# DM1090FFC_USB.net
KiCad netlist of a schematic drawn in Altium Designer
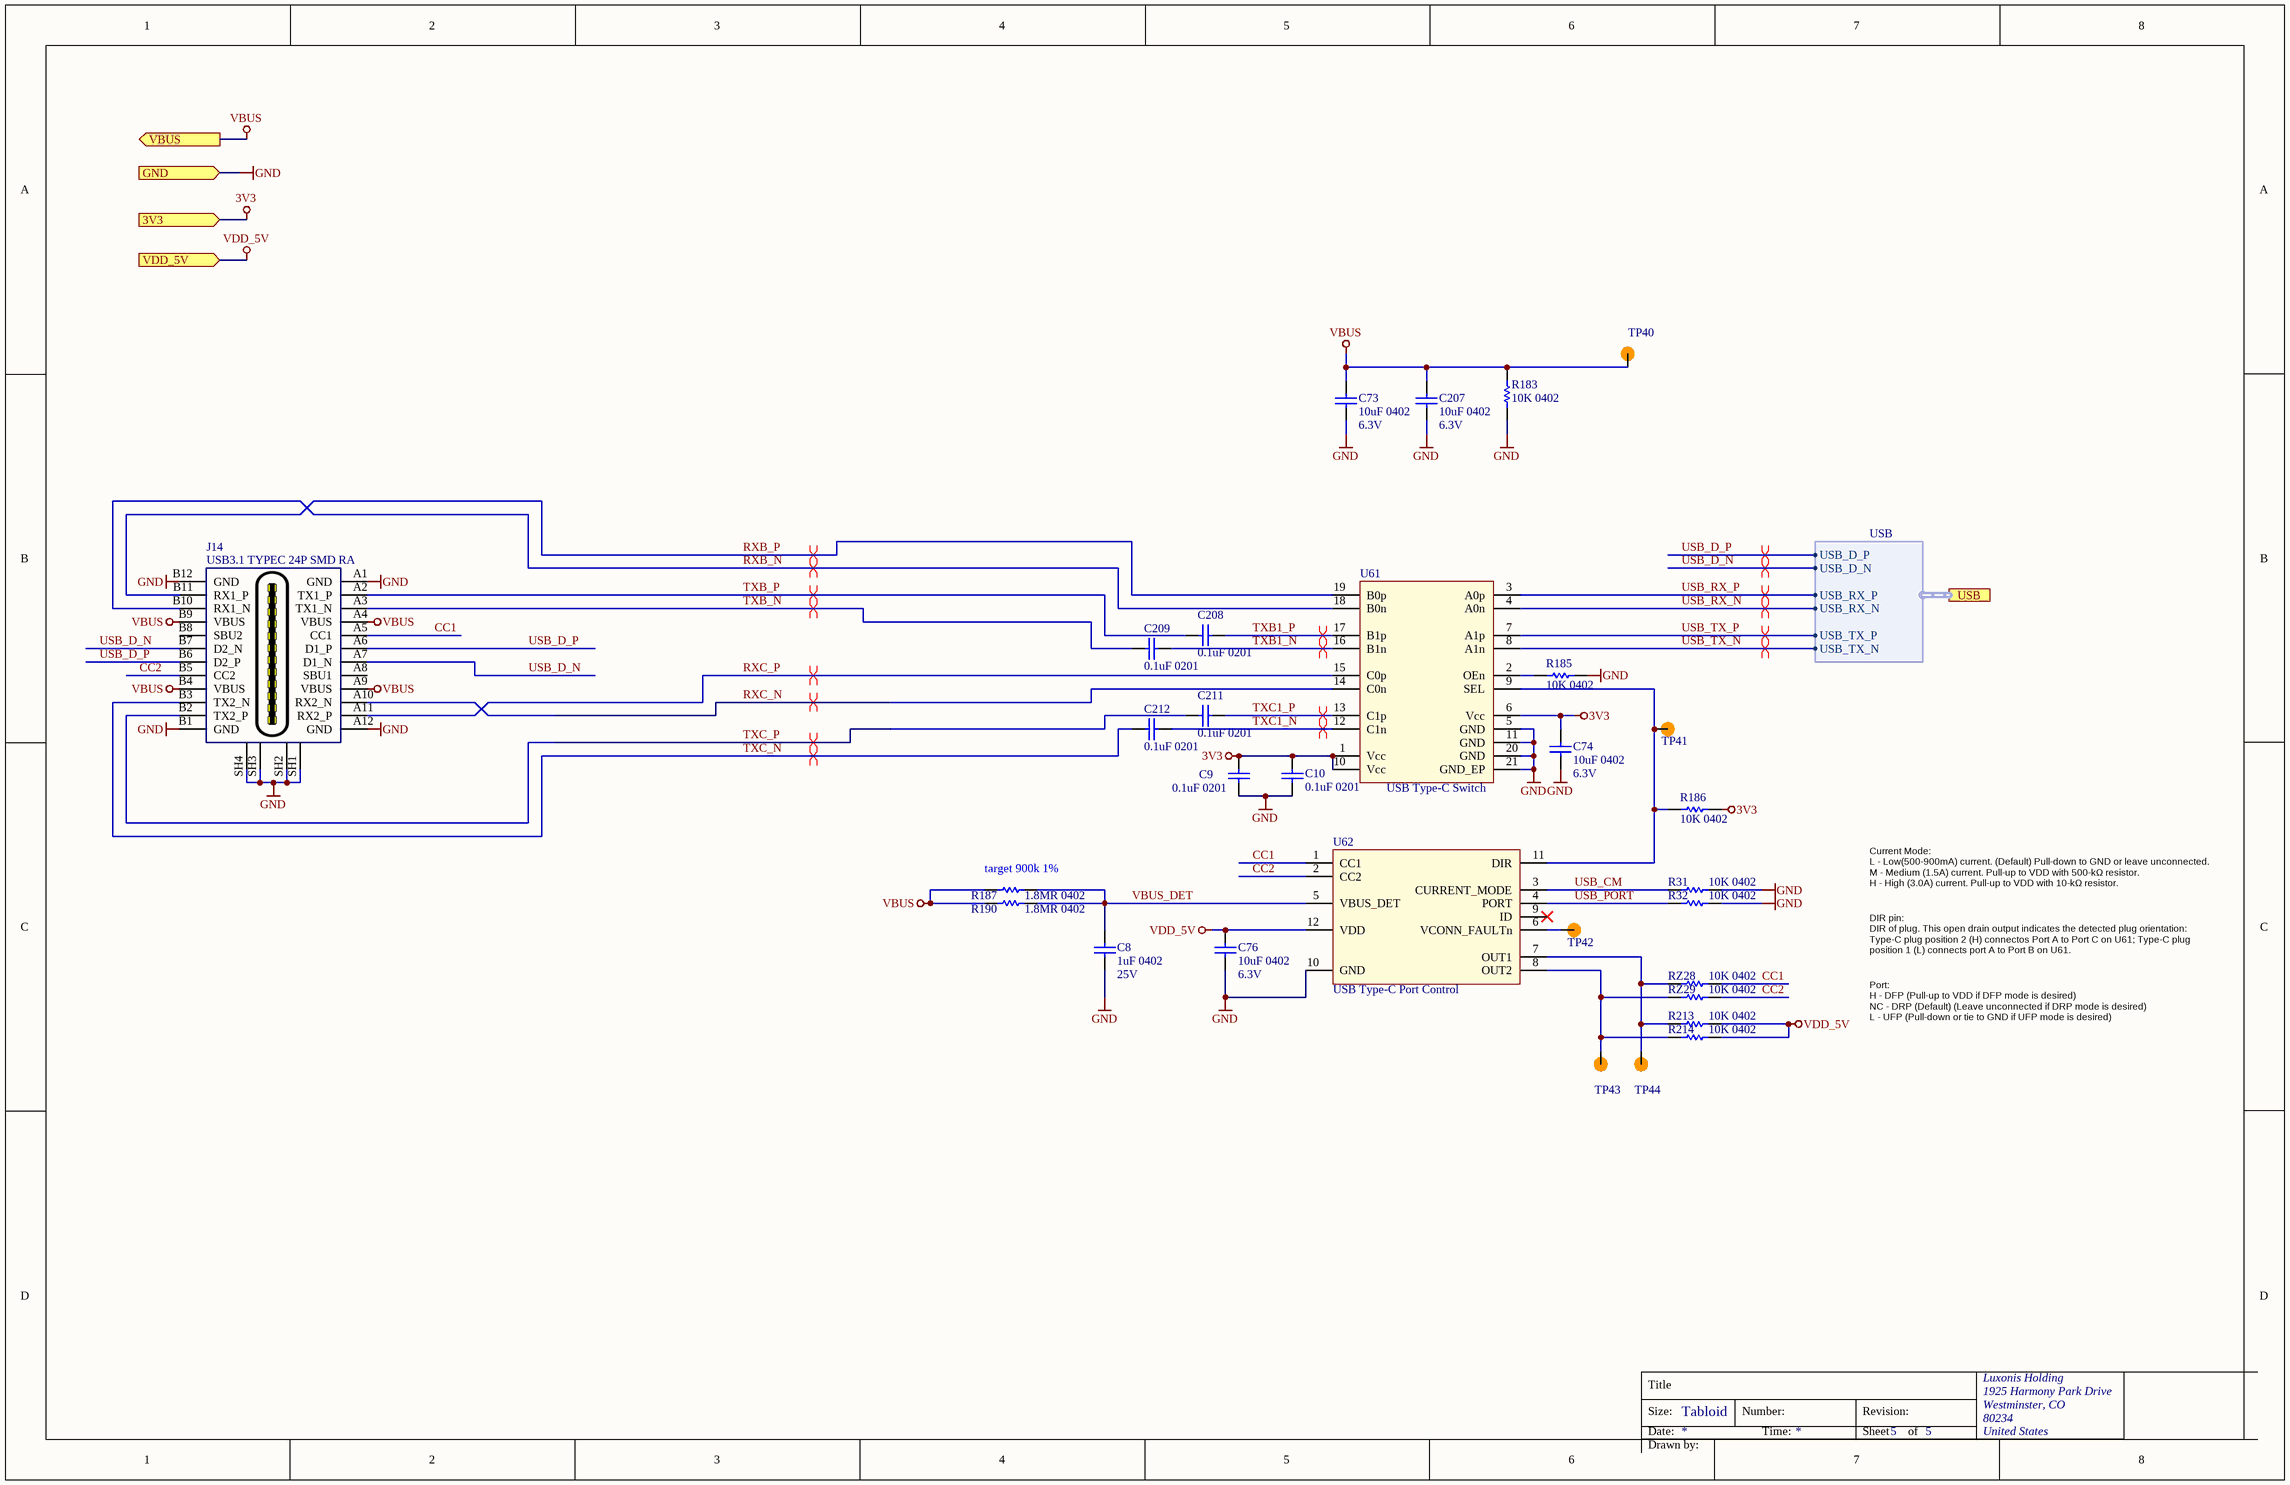
[diagram p0: DM1090FFC_USB.SchDoc]

(export (version "E")
  (design (tool "Eeschema 10.0.6"))
  (components
    (comp (ref "C8")
      (value "1uF 0402")
      (footprint "CAP_Altium_Vault_Generic:CAPC0402(1005)70_N")
      (description "CAP CER 1UF 25V X5R 0402 10%")
      (fields
        (field (name "TOLERANCE") "10%")
        (field (name "VOLTAGE") "25V")
        (field (name "VOLTAGE RATING") "25V")
      )
      (libsource (lib "LuxonisMaster") (part "GRM155R61E105KA12D"))
    )
    (comp (ref "C9")
      (value "0.1uF 0201")
      (footprint "CAP_Altium_Vault_Generic:CAPC0201(0603)33_L")
      (description "CAP CER 0.1UF 10V X5R 0201")
      (fields (field (name "TOLERANCE") "10%") (field (name "VOLTAGE") "10V"))
      (libsource (lib "LuxonisMaster") (part "GRM033R61A104KE15D"))
    )
    (comp (ref "C10")
      (value "0.1uF 0201")
      (footprint "CAP_Altium_Vault_Generic:CAPC0201(0603)33_L")
      (description "CAP CER 0.1UF 10V X5R 0201")
      (fields (field (name "TOLERANCE") "10%") (field (name "VOLTAGE") "10V"))
      (libsource (lib "LuxonisMaster") (part "GRM033R61A104KE15D"))
    )
    (comp (ref "C73")
      (value "10uF 0402")
      (footprint "CAP_Altium_Vault_Generic:CAPC0402(1005)70_N")
      (description "CAP CER 10UF 6.3V X5R 0402 20%")
      (fields (field (name "TOLERANCE") "20%") (field (name "VOLTAGE RATING") "6.3V"))
      (libsource (lib "LuxonisMaster") (part "GRM155R60J106ME15D"))
    )
    (comp (ref "C74")
      (value "10uF 0402")
      (footprint "CAP_Altium_Vault_Generic:CAPC0402(1005)70_N")
      (description "CAP CER 10UF 6.3V X5R 0402 20%")
      (fields (field (name "TOLERANCE") "20%") (field (name "VOLTAGE RATING") "6.3V"))
      (libsource (lib "LuxonisMaster") (part "GRM155R60J106ME15D"))
    )
    (comp (ref "C76")
      (value "10uF 0402")
      (footprint "CAP_Altium_Vault_Generic:CAPC0402(1005)70_N")
      (description "CAP CER 10UF 6.3V X5R 0402 20%")
      (fields (field (name "TOLERANCE") "20%") (field (name "VOLTAGE RATING") "6.3V"))
      (libsource (lib "LuxonisMaster") (part "GRM155R60J106ME15D"))
    )
    (comp (ref "C207")
      (value "10uF 0402")
      (footprint "CAP_Altium_Vault_Generic:CAPC0402(1005)70_N")
      (description "CAP CER 10UF 6.3V X5R 0402 20%")
      (fields (field (name "TOLERANCE") "20%") (field (name "VOLTAGE RATING") "6.3V"))
      (libsource (lib "LuxonisMaster") (part "GRM155R60J106ME15D"))
    )
    (comp (ref "C208")
      (value "0.1uF 0201")
      (footprint "CAP_Altium_Vault_Generic:CAPC0201(0603)33_L")
      (description "CAP CER 0.1UF 10V X5R 0201")
      (fields (field (name "TOLERANCE") "10%") (field (name "VOLTAGE") "10V"))
      (libsource (lib "LuxonisMaster") (part "GRM033R61A104KE15D"))
    )
    (comp (ref "C209")
      (value "0.1uF 0201")
      (footprint "CAP_Altium_Vault_Generic:CAPC0201(0603)33_L")
      (description "CAP CER 0.1UF 10V X5R 0201")
      (fields (field (name "TOLERANCE") "10%") (field (name "VOLTAGE") "10V"))
      (libsource (lib "LuxonisMaster") (part "GRM033R61A104KE15D"))
    )
    (comp (ref "C211")
      (value "0.1uF 0201")
      (footprint "CAP_Altium_Vault_Generic:CAPC0201(0603)33_L")
      (description "CAP CER 0.1UF 10V X5R 0201")
      (fields (field (name "TOLERANCE") "10%") (field (name "VOLTAGE") "10V"))
      (libsource (lib "LuxonisMaster") (part "GRM033R61A104KE15D"))
    )
    (comp (ref "C212")
      (value "0.1uF 0201")
      (footprint "CAP_Altium_Vault_Generic:CAPC0201(0603)33_L")
      (description "CAP CER 0.1UF 10V X5R 0201")
      (fields (field (name "TOLERANCE") "10%") (field (name "VOLTAGE") "10V"))
      (libsource (lib "LuxonisMaster") (part "GRM033R61A104KE15D"))
    )
    (comp (ref "J14")
      (value "USB3.1 TYPEC 24P SMD RA")
      (footprint "LuxonisMaster:105450-0101")
      (description "CONN RCP USB3.1 TYPEC 24P SMD RA")
      (libsource (lib "LuxonisMaster") (part "105450-0101"))
    )
    (comp (ref "R31")
      (value "10K 0402")
      (footprint "RES_Altium_Vault_Generic:RESC0402(1005)_N")
      (fields (field (name "TOLERANCE") "1%"))
      (libsource (lib "LuxonisMaster") (part "RC0402FR-1310KL"))
    )
    (comp (ref "R32")
      (value "10K 0402")
      (footprint "RES_Altium_Vault_Generic:RESC0402(1005)_N")
      (fields (field (name "TOLERANCE") "1%"))
      (libsource (lib "LuxonisMaster") (part "RC0402FR-1310KL"))
    )
    (comp (ref "R183")
      (value "10K 0402")
      (footprint "RES_Altium_Vault_Generic:RESC0402(1005)_N")
      (fields (field (name "TOLERANCE") "1%"))
      (libsource (lib "LuxonisMaster") (part "RC0402FR-1310KL"))
    )
    (comp (ref "R185")
      (value "10K 0402")
      (footprint "RES_Altium_Vault_Generic:RESC0402(1005)_N")
      (fields (field (name "TOLERANCE") "1%"))
      (libsource (lib "LuxonisMaster") (part "RC0402FR-1310KL"))
    )
    (comp (ref "R186")
      (value "10K 0402")
      (footprint "RES_Altium_Vault_Generic:RESC0402(1005)_N")
      (fields (field (name "TOLERANCE") "1%"))
      (libsource (lib "LuxonisMaster") (part "RC0402FR-1310KL"))
    )
    (comp (ref "R187")
      (value "1.8MR 0402")
      (footprint "RES_Altium_Vault_Generic:RESC0402(1005)_N")
      (description "RES SMD 1.8M OHM 1% 1/16W 0402")
      (fields (field (name "TOLERANCE") "1%"))
      (libsource (lib "LuxonisMaster") (part "CRCW04021M80FKED"))
    )
    (comp (ref "R190")
      (value "1.8MR 0402")
      (footprint "RES_Altium_Vault_Generic:RESC0402(1005)_N")
      (description "RES SMD 1.8M OHM 1% 1/16W 0402")
      (fields (field (name "TOLERANCE") "1%"))
      (libsource (lib "LuxonisMaster") (part "CRCW04021M80FKED"))
    )
    (comp (ref "R213")
      (value "10K 0402")
      (footprint "RES_Altium_Vault_Generic:RESC0402(1005)_N")
      (fields (field (name "TOLERANCE") "1%"))
      (libsource (lib "LuxonisMaster") (part "RC0402FR-1310KL"))
    )
    (comp (ref "R214")
      (value "10K 0402")
      (footprint "RES_Altium_Vault_Generic:RESC0402(1005)_N")
      (fields (field (name "TOLERANCE") "1%"))
      (libsource (lib "LuxonisMaster") (part "RC0402FR-1310KL"))
    )
    (comp (ref "RZ28")
      (value "10K 0402")
      (footprint "RES_Altium_Vault_Generic:RESC0402(1005)_N")
      (fields (field (name "TOLERANCE") "1%"))
      (libsource (lib "LuxonisMaster") (part "RC0402FR-1310KL"))
    )
    (comp (ref "RZ29")
      (value "10K 0402")
      (footprint "RES_Altium_Vault_Generic:RESC0402(1005)_N")
      (fields (field (name "TOLERANCE") "1%"))
      (libsource (lib "LuxonisMaster") (part "RC0402FR-1310KL"))
    )
    (comp (ref "TP40")
      (value "TP100_200_NS")
      (footprint "LuxonisMaster:TP100_200_NS")
      (libsource (lib "LuxonisMaster") (part "TEST_POINT"))
    )
    (comp (ref "TP41")
      (value "TP100_200_NS")
      (footprint "LuxonisMaster:TP100_200_NS")
      (libsource (lib "LuxonisMaster") (part "TEST_POINT"))
    )
    (comp (ref "TP42")
      (value "TP100_200_NS")
      (footprint "LuxonisMaster:TP100_200_NS")
      (libsource (lib "LuxonisMaster") (part "TEST_POINT"))
    )
    (comp (ref "TP43")
      (value "TP100_200_NS")
      (footprint "LuxonisMaster:TP100_200_NS")
      (libsource (lib "LuxonisMaster") (part "TEST_POINT"))
    )
    (comp (ref "TP44")
      (value "TP100_200_NS")
      (footprint "LuxonisMaster:TP100_200_NS")
      (libsource (lib "LuxonisMaster") (part "TEST_POINT"))
    )
    (comp (ref "U61")
      (value "USB Type-C Switch")
      (footprint "CBTL02043A")
      (libsource (lib "LuxonisMaster") (part "CBTL02043A"))
    )
    (comp (ref "U62")
      (value "USB Type-C Port Control")
      (footprint "LuxonisMaster:TUSB321RWBR")
      (description "IC USB PORT CONTROL TYPE-C 12X2Q")
      (libsource (lib "LuxonisMaster") (part "TUSB321RWBR"))
    )
  )
  (nets
    (net (code "2") (name "/CC1") (class "Default")
      (node (ref "J14") (pin "A5") (pinfunction "CC1_A5") (pintype "passive"))
      (node (ref "RZ28") (pin "2") (pinfunction "2_2") (pintype "passive"))
      (node (ref "U62") (pin "1") (pinfunction "CC1_1") (pintype "passive"))
    )
    (net (code "3") (name "/CC2") (class "Default")
      (node (ref "J14") (pin "B5") (pinfunction "CC2_B5") (pintype "passive"))
      (node (ref "RZ29") (pin "2") (pinfunction "2_2") (pintype "passive"))
      (node (ref "U62") (pin "2") (pinfunction "CC2_2") (pintype "passive"))
    )
    (net (code "4") (name "/RXB_N") (class "Default")
      (node (ref "J14") (pin "B10") (pinfunction "RX1_N_B10") (pintype "passive"))
      (node (ref "U61") (pin "18") (pinfunction "B0n_18") (pintype "passive"))
    )
    (net (code "5") (name "/RXB_P") (class "Default")
      (node (ref "J14") (pin "B11") (pinfunction "RX1_P_B11") (pintype "passive"))
      (node (ref "U61") (pin "19") (pinfunction "B0p_19") (pintype "passive"))
    )
    (net (code "6") (name "/RXC_N") (class "Default")
      (node (ref "J14") (pin "A10") (pinfunction "RX2_N_A10") (pintype "passive"))
      (node (ref "U61") (pin "14") (pinfunction "C0n_14") (pintype "passive"))
    )
    (net (code "7") (name "/RXC_P") (class "Default")
      (node (ref "J14") (pin "A11") (pinfunction "RX2_P_A11") (pintype "passive"))
      (node (ref "U61") (pin "15") (pinfunction "C0p_15") (pintype "passive"))
    )
    (net (code "8") (name "/TXB1_N") (class "Default")
      (node (ref "C209") (pin "2") (pinfunction "2_2") (pintype "passive"))
      (node (ref "U61") (pin "16") (pinfunction "B1n_16") (pintype "passive"))
    )
    (net (code "9") (name "/TXB1_P") (class "Default")
      (node (ref "C208") (pin "2") (pinfunction "2_2") (pintype "passive"))
      (node (ref "U61") (pin "17") (pinfunction "B1p_17") (pintype "passive"))
    )
    (net (code "10") (name "/TXB_N") (class "Default")
      (node (ref "C209") (pin "1") (pinfunction "1_1") (pintype "passive"))
      (node (ref "J14") (pin "A3") (pinfunction "TX1_N_A3") (pintype "passive"))
    )
    (net (code "11") (name "/TXB_P") (class "Default")
      (node (ref "C208") (pin "1") (pinfunction "1_1") (pintype "passive"))
      (node (ref "J14") (pin "A2") (pinfunction "TX1_P_A2") (pintype "passive"))
    )
    (net (code "12") (name "/TXC1_N") (class "Default")
      (node (ref "C212") (pin "2") (pinfunction "2_2") (pintype "passive"))
      (node (ref "U61") (pin "12") (pinfunction "C1n_12") (pintype "passive"))
    )
    (net (code "13") (name "/TXC1_P") (class "Default")
      (node (ref "C211") (pin "2") (pinfunction "2_2") (pintype "passive"))
      (node (ref "U61") (pin "13") (pinfunction "C1p_13") (pintype "passive"))
    )
    (net (code "14") (name "/TXC_N") (class "Default")
      (node (ref "C212") (pin "1") (pinfunction "1_1") (pintype "passive"))
      (node (ref "J14") (pin "B3") (pinfunction "TX2_N_B3") (pintype "passive"))
    )
    (net (code "15") (name "/TXC_P") (class "Default")
      (node (ref "C211") (pin "1") (pinfunction "1_1") (pintype "passive"))
      (node (ref "J14") (pin "B2") (pinfunction "TX2_P_B2") (pintype "passive"))
    )
    (net (code "16") (name "/USB_CM") (class "Default")
      (node (ref "R31") (pin "1") (pinfunction "1_1") (pintype "passive"))
      (node (ref "U62") (pin "3") (pinfunction "CURRENT_MODE_3") (pintype "passive"))
    )
    (net (code "17") (name "/USB_D_N") (class "Default")
      (node (ref "J14") (pin "A7") (pinfunction "D1_N_A7") (pintype "passive"))
      (node (ref "J14") (pin "B7") (pinfunction "D2_N_B7") (pintype "passive"))
    )
    (net (code "18") (name "/USB_D_P") (class "Default")
      (node (ref "J14") (pin "A6") (pinfunction "D1_P_A6") (pintype "passive"))
      (node (ref "J14") (pin "B6") (pinfunction "D2_P_B6") (pintype "passive"))
    )
    (net (code "19") (name "/USB_PORT") (class "Default")
      (node (ref "R32") (pin "1") (pinfunction "1_1") (pintype "passive"))
      (node (ref "U62") (pin "4") (pinfunction "PORT_4") (pintype "passive"))
    )
    (net (code "20") (name "/USB_RX_N") (class "Default")
      (node (ref "U61") (pin "4") (pinfunction "A0n_4") (pintype "passive"))
    )
    (net (code "21") (name "/USB_RX_P") (class "Default")
      (node (ref "U61") (pin "3") (pinfunction "A0p_3") (pintype "passive"))
    )
    (net (code "22") (name "/USB_TX_N") (class "Default")
      (node (ref "U61") (pin "8") (pinfunction "A1n_8") (pintype "passive"))
    )
    (net (code "23") (name "/USB_TX_P") (class "Default")
      (node (ref "U61") (pin "7") (pinfunction "A1p_7") (pintype "passive"))
    )
    (net (code "24") (name "/VBUS_DET") (class "Default")
      (node (ref "C8") (pin "2") (pinfunction "2_2") (pintype "passive"))
      (node (ref "R187") (pin "2") (pinfunction "2_2") (pintype "passive"))
      (node (ref "R190") (pin "2") (pinfunction "2_2") (pintype "passive"))
      (node (ref "U62") (pin "5") (pinfunction "VBUS_DET_5") (pintype "passive"))
    )
    (net (code "26") (name "3V3") (class "Default")
      (node (ref "C10") (pin "2") (pinfunction "2_2") (pintype "passive"))
      (node (ref "C74") (pin "2") (pinfunction "2_2") (pintype "passive"))
      (node (ref "C9") (pin "2") (pinfunction "2_2") (pintype "passive"))
      (node (ref "R186") (pin "2") (pinfunction "2_2") (pintype "passive"))
      (node (ref "U61") (pin "1") (pinfunction "Vcc_1") (pintype "passive"))
      (node (ref "U61") (pin "10") (pinfunction "Vcc_10") (pintype "passive"))
      (node (ref "U61") (pin "6") (pinfunction "Vcc_6") (pintype "passive"))
    )
    (net (code "27") (name "GND") (class "Default")
      (node (ref "C10") (pin "1") (pinfunction "1_1") (pintype "passive"))
      (node (ref "C207") (pin "1") (pinfunction "1_1") (pintype "passive"))
      (node (ref "C73") (pin "1") (pinfunction "1_1") (pintype "passive"))
      (node (ref "C74") (pin "1") (pinfunction "1_1") (pintype "passive"))
      (node (ref "C76") (pin "1") (pinfunction "1_1") (pintype "passive"))
      (node (ref "C8") (pin "1") (pinfunction "1_1") (pintype "passive"))
      (node (ref "C9") (pin "1") (pinfunction "1_1") (pintype "passive"))
      (node (ref "J14") (pin "A1") (pinfunction "GND_A1") (pintype "passive"))
      (node (ref "J14") (pin "A12") (pinfunction "GND_A12") (pintype "passive"))
      (node (ref "J14") (pin "B1") (pinfunction "GND_B1") (pintype "passive"))
      (node (ref "J14") (pin "B12") (pinfunction "GND_B12") (pintype "passive"))
      (node (ref "J14") (pin "SH1") (pinfunction "SH_SH1") (pintype "passive"))
      (node (ref "J14") (pin "SH2") (pinfunction "SH_SH2") (pintype "passive"))
      (node (ref "J14") (pin "SH3") (pinfunction "SH_SH3") (pintype "passive"))
      (node (ref "J14") (pin "SH4") (pinfunction "SH_SH4") (pintype "passive"))
      (node (ref "R183") (pin "1") (pinfunction "1_1") (pintype "passive"))
      (node (ref "R185") (pin "2") (pinfunction "2_2") (pintype "passive"))
      (node (ref "R31") (pin "2") (pinfunction "2_2") (pintype "passive"))
      (node (ref "R32") (pin "2") (pinfunction "2_2") (pintype "passive"))
      (node (ref "U61") (pin "11") (pinfunction "GND_11") (pintype "passive"))
      (node (ref "U61") (pin "20") (pinfunction "GND_20") (pintype "passive"))
      (node (ref "U61") (pin "21") (pinfunction "GND_EP_21") (pintype "passive"))
      (node (ref "U61") (pin "5") (pinfunction "GND_5") (pintype "passive"))
      (node (ref "U62") (pin "10") (pinfunction "GND_10") (pintype "passive"))
    )
    (net (code "28") (name "Net-(U61-OEn)") (class "Default")
      (node (ref "R185") (pin "1") (pinfunction "1_1") (pintype "passive"))
      (node (ref "U61") (pin "2") (pinfunction "OEn_2") (pintype "passive"))
    )
    (net (code "29") (name "Net-(U61-SEL)") (class "Default")
      (node (ref "R186") (pin "1") (pinfunction "1_1") (pintype "passive"))
      (node (ref "TP41") (pin "1") (pintype "passive"))
      (node (ref "U61") (pin "9") (pinfunction "SEL_9") (pintype "passive"))
      (node (ref "U62") (pin "11") (pinfunction "DIR_11") (pintype "passive"))
    )
    (net (code "30") (name "Net-(U62-OUT1)") (class "Default")
      (node (ref "R213") (pin "1") (pinfunction "1_1") (pintype "passive"))
      (node (ref "RZ28") (pin "1") (pinfunction "1_1") (pintype "passive"))
      (node (ref "TP44") (pin "1") (pintype "passive"))
      (node (ref "U62") (pin "7") (pinfunction "OUT1_7") (pintype "passive"))
    )
    (net (code "31") (name "Net-(U62-OUT2)") (class "Default")
      (node (ref "R214") (pin "1") (pinfunction "1_1") (pintype "passive"))
      (node (ref "RZ29") (pin "1") (pinfunction "1_1") (pintype "passive"))
      (node (ref "TP43") (pin "1") (pintype "passive"))
      (node (ref "U62") (pin "8") (pinfunction "OUT2_8") (pintype "passive"))
    )
    (net (code "32") (name "Net-(U62-VCONN_FAULTn)") (class "Default")
      (node (ref "TP42") (pin "1") (pintype "passive"))
      (node (ref "U62") (pin "6") (pinfunction "VCONN_FAULTn_6") (pintype "passive"))
    )
    (net (code "33") (name "VBUS") (class "Default")
      (node (ref "C207") (pin "2") (pinfunction "2_2") (pintype "passive"))
      (node (ref "C73") (pin "2") (pinfunction "2_2") (pintype "passive"))
      (node (ref "J14") (pin "A4") (pinfunction "VBUS_A4") (pintype "passive"))
      (node (ref "J14") (pin "A9") (pinfunction "VBUS_A9") (pintype "passive"))
      (node (ref "J14") (pin "B4") (pinfunction "VBUS_B4") (pintype "passive"))
      (node (ref "J14") (pin "B9") (pinfunction "VBUS_B9") (pintype "passive"))
      (node (ref "R183") (pin "2") (pinfunction "2_2") (pintype "passive"))
      (node (ref "R187") (pin "1") (pinfunction "1_1") (pintype "passive"))
      (node (ref "R190") (pin "1") (pinfunction "1_1") (pintype "passive"))
      (node (ref "TP40") (pin "1") (pintype "passive"))
    )
    (net (code "34") (name "VDD_5V") (class "Default")
      (node (ref "C76") (pin "2") (pinfunction "2_2") (pintype "passive"))
      (node (ref "R213") (pin "2") (pinfunction "2_2") (pintype "passive"))
      (node (ref "R214") (pin "2") (pinfunction "2_2") (pintype "passive"))
      (node (ref "U62") (pin "12") (pinfunction "VDD_12") (pintype "passive"))
    )
    (net (code "35") (name "unconnected-(J14-SBU1-PadA8)") (class "Default")
      (node (ref "J14") (pin "A8") (pinfunction "SBU1_A8") (pintype "passive"))
    )
    (net (code "36") (name "unconnected-(J14-SBU2-PadB8)") (class "Default")
      (node (ref "J14") (pin "B8") (pinfunction "SBU2_B8") (pintype "passive"))
    )
    (net (code "37") (name "unconnected-(U62-ID-Pad9)") (class "Default")
      (node (ref "U62") (pin "9") (pinfunction "ID_9") (pintype "passive+no_connect"))
    )
  )
)
